# charging_circuit.net
KiCad netlist of a schematic drawn in EAGLE
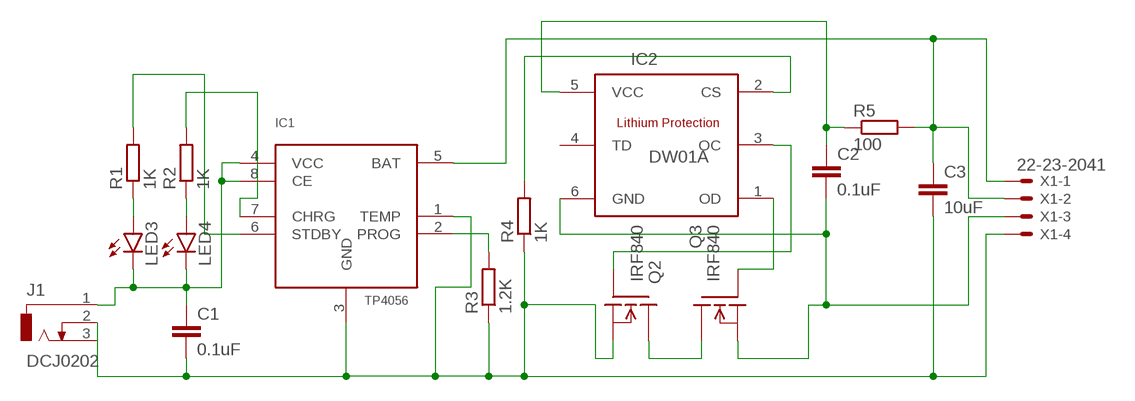
[diagram p0: schematic, sheet 1]

(export (version "E")
  (design (tool "Eeschema 10.0.6"))
  (components
    (comp (ref "C1")
      (value "0.1uF")
      (footprint "eagle-import:C0805")
      (libsource (lib "eagle-import") (part "C-EUC0805"))
    )
    (comp (ref "C2")
      (value "0.1uF")
      (footprint "eagle-import:C0805")
      (libsource (lib "eagle-import") (part "C-EUC0805"))
    )
    (comp (ref "C3")
      (value "10uF")
      (footprint "eagle-import:C0805")
      (libsource (lib "eagle-import") (part "C-EUC0805"))
    )
    (comp (ref "IC1")
      (value "TP4056")
      (footprint "eagle-import:SOP-8")
      (fields (field (name "MF") "NanJing Top Power ASIC Corp.") (field (name "MP") "TP4056 "))
      (libsource (lib "eagle-import") (part "TP4056"))
    )
    (comp (ref "IC2")
      (value "DW01A")
      (footprint "eagle-import:SOT23-6")
      (fields (field (name "MF") "Fortune Semiconductor"))
      (libsource (lib "eagle-import") (part "DW01A"))
    )
    (comp (ref "J1")
      (value "DCJ0202")
      (footprint "eagle-import:DCJ0202")
      (libsource (lib "eagle-import") (part "DCJ0202"))
    )
    (comp (ref "LED3")
      (value "LEDCHIP-LED0805")
      (footprint "eagle-import:CHIP-LED0805")
      (libsource (lib "eagle-import") (part "LEDCHIP-LED0805"))
    )
    (comp (ref "LED4")
      (value "LEDCHIP-LED0805")
      (footprint "eagle-import:CHIP-LED0805")
      (libsource (lib "eagle-import") (part "LEDCHIP-LED0805"))
    )
    (comp (ref "Q2")
      (value "IRF840")
      (footprint "eagle-import:TO220")
      (libsource (lib "eagle-import") (part "IRF840"))
    )
    (comp (ref "Q3")
      (value "IRF840")
      (footprint "eagle-import:TO220")
      (libsource (lib "eagle-import") (part "IRF840"))
    )
    (comp (ref "R1")
      (value "1K")
      (footprint "eagle-import:0207_10")
      (libsource (lib "eagle-import") (part "R-EU_0207/10"))
    )
    (comp (ref "R2")
      (value "1K")
      (footprint "eagle-import:0207_10")
      (libsource (lib "eagle-import") (part "R-EU_0207/10"))
    )
    (comp (ref "R3")
      (value "1.2K")
      (footprint "eagle-import:0207_10")
      (libsource (lib "eagle-import") (part "R-EU_0207/10"))
    )
    (comp (ref "R4")
      (value "1K")
      (footprint "eagle-import:0207_10")
      (libsource (lib "eagle-import") (part "R-EU_0207/10"))
    )
    (comp (ref "R5")
      (value "100")
      (footprint "eagle-import:0207_10")
      (libsource (lib "eagle-import") (part "R-EU_0207/10"))
    )
    (comp (ref "X1")
      (value "22-23-2041")
      (footprint "eagle-import:22-23-2041")
      (fields (field (name "MF") "MOLEX"))
      (libsource (lib "eagle-import") (part "22-23-2041"))
    )
  )
  (nets
    (net (code "1") (name "Net-(IC1-BAT)") (class "Default")
      (node (ref "C3") (pin "1") (pinfunction "1_1") (pintype "passive"))
      (node (ref "IC1") (pin "5") (pinfunction "BAT_5") (pintype "bidirectional"))
      (node (ref "R5") (pin "2") (pinfunction "2_2") (pintype "passive"))
      (node (ref "X1") (pin "1") (pinfunction "S_1") (pintype "passive"))
      (node (ref "X1") (pin "2") (pinfunction "S_2") (pintype "passive"))
    )
    (net (code "2") (name "Net-(IC1-CE)") (class "Default")
      (node (ref "C1") (pin "1") (pinfunction "1_1") (pintype "passive"))
      (node (ref "IC1") (pin "4") (pinfunction "VCC_4") (pintype "bidirectional"))
      (node (ref "IC1") (pin "8") (pinfunction "CE_8") (pintype "bidirectional"))
      (node (ref "J1") (pin "1") (pinfunction "1_1") (pintype "passive"))
      (node (ref "LED3") (pin "C") (pinfunction "C_C") (pintype "passive"))
      (node (ref "LED4") (pin "C") (pinfunction "C_C") (pintype "passive"))
    )
    (net (code "3") (name "Net-(IC1-CHRG)") (class "Default")
      (node (ref "IC1") (pin "7") (pinfunction "CHRG_7") (pintype "bidirectional"))
      (node (ref "R2") (pin "2") (pinfunction "2_2") (pintype "passive"))
    )
    (net (code "4") (name "Net-(IC1-GND)") (class "Default")
      (node (ref "C1") (pin "2") (pinfunction "2_2") (pintype "passive"))
      (node (ref "C3") (pin "2") (pinfunction "2_2") (pintype "passive"))
      (node (ref "IC1") (pin "1") (pinfunction "TEMP_1") (pintype "bidirectional"))
      (node (ref "IC1") (pin "3") (pinfunction "GND_3") (pintype "bidirectional"))
      (node (ref "J1") (pin "2") (pinfunction "2_2") (pintype "passive"))
      (node (ref "J1") (pin "3") (pinfunction "3_3") (pintype "passive"))
      (node (ref "Q2") (pin "3") (pinfunction "S_3") (pintype "passive"))
      (node (ref "R3") (pin "1") (pinfunction "1_1") (pintype "passive"))
      (node (ref "R4") (pin "1") (pinfunction "1_1") (pintype "passive"))
      (node (ref "X1") (pin "4") (pinfunction "S_4") (pintype "passive"))
    )
    (net (code "5") (name "Net-(IC1-PROG)") (class "Default")
      (node (ref "IC1") (pin "2") (pinfunction "PROG_2") (pintype "bidirectional"))
      (node (ref "R3") (pin "2") (pinfunction "2_2") (pintype "passive"))
    )
    (net (code "6") (name "Net-(IC1-STDBY)") (class "Default")
      (node (ref "IC1") (pin "6") (pinfunction "STDBY_6") (pintype "bidirectional"))
      (node (ref "R1") (pin "2") (pinfunction "2_2") (pintype "passive"))
    )
    (net (code "7") (name "Net-(IC2-CS)") (class "Default")
      (node (ref "IC2") (pin "2") (pinfunction "CS_2") (pintype "bidirectional"))
      (node (ref "R4") (pin "2") (pinfunction "2_2") (pintype "passive"))
    )
    (net (code "8") (name "Net-(IC2-GND)") (class "Default")
      (node (ref "C2") (pin "2") (pinfunction "2_2") (pintype "passive"))
      (node (ref "IC2") (pin "6") (pinfunction "GND_6") (pintype "power_in"))
      (node (ref "Q3") (pin "3") (pinfunction "S_3") (pintype "passive"))
      (node (ref "X1") (pin "3") (pinfunction "S_3") (pintype "passive"))
    )
    (net (code "9") (name "Net-(IC2-OC)") (class "Default")
      (node (ref "IC2") (pin "3") (pinfunction "OC_3") (pintype "bidirectional"))
      (node (ref "Q2") (pin "1") (pinfunction "G_1") (pintype "passive"))
    )
    (net (code "10") (name "Net-(IC2-OD)") (class "Default")
      (node (ref "IC2") (pin "1") (pinfunction "OD_1") (pintype "bidirectional"))
      (node (ref "Q3") (pin "1") (pinfunction "G_1") (pintype "passive"))
    )
    (net (code "11") (name "Net-(IC2-VCC)") (class "Default")
      (node (ref "C2") (pin "1") (pinfunction "1_1") (pintype "passive"))
      (node (ref "IC2") (pin "5") (pinfunction "VCC_5") (pintype "power_in"))
      (node (ref "R5") (pin "1") (pinfunction "1_1") (pintype "passive"))
    )
    (net (code "12") (name "Net-(LED3-PadA)") (class "Default")
      (node (ref "LED3") (pin "A") (pinfunction "A_A") (pintype "passive"))
      (node (ref "R1") (pin "1") (pinfunction "1_1") (pintype "passive"))
    )
    (net (code "13") (name "Net-(LED4-PadA)") (class "Default")
      (node (ref "LED4") (pin "A") (pinfunction "A_A") (pintype "passive"))
      (node (ref "R2") (pin "1") (pinfunction "1_1") (pintype "passive"))
    )
    (net (code "14") (name "Net-(Q2-D)") (class "Default")
      (node (ref "Q2") (pin "2") (pinfunction "D_2") (pintype "passive"))
      (node (ref "Q3") (pin "2") (pinfunction "D_2") (pintype "passive"))
    )
    (net (code "15") (name "unconnected-(IC2-TD-Pad4)") (class "Default")
      (node (ref "IC2") (pin "4") (pinfunction "TD_4") (pintype "bidirectional"))
    )
  )
)
